# PM12_P3V3.net
KiCad netlist of a schematic drawn in Altium Designer
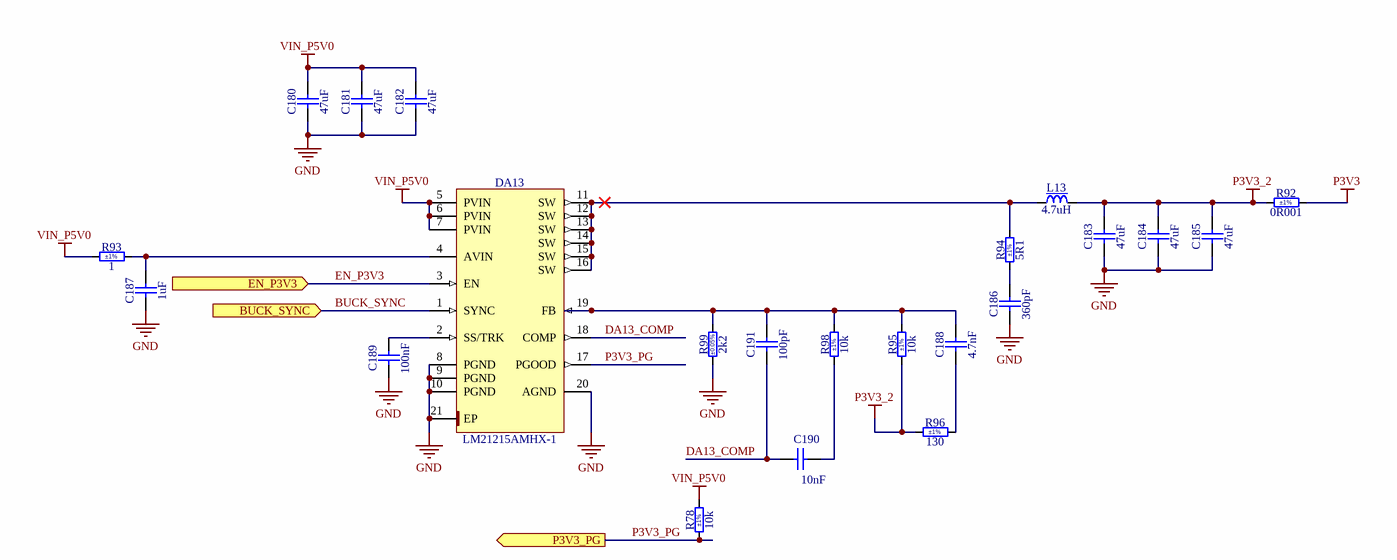
[diagram p0: PM12_P3V3.SchDoc]

(export (version "E")
  (design (tool "Eeschema 10.0.6"))
  (components
    (comp (ref "C180")
      (value "47uF")
      (footprint "CAPC3225X270N")
      (description "Non-polarised capacitor")
      (fields
        (field (name "PART NUMBER") "CC1210_47UF_16V_20%_X5R")
        (field (name "VOLTAGE") "16V")
        (field (name "AUTHOR") "CERN DEM MR")
      )
      (libsource (lib "Capacitors") (part "Capacitor - non polarized"))
    )
    (comp (ref "C181")
      (value "47uF")
      (footprint "CAPC3225X270N")
      (description "Non-polarised capacitor")
      (fields
        (field (name "PART NUMBER") "CC1210_47UF_16V_20%_X5R")
        (field (name "VOLTAGE") "16V")
        (field (name "AUTHOR") "CERN DEM MR")
      )
      (libsource (lib "Capacitors") (part "Capacitor - non polarized"))
    )
    (comp (ref "C182")
      (value "47uF")
      (footprint "CAPC3225X270N")
      (description "Non-polarised capacitor")
      (fields
        (field (name "PART NUMBER") "CC1210_47UF_16V_20%_X5R")
        (field (name "VOLTAGE") "16V")
        (field (name "AUTHOR") "CERN DEM MR")
      )
      (libsource (lib "Capacitors") (part "Capacitor - non polarized"))
    )
    (comp (ref "C183")
      (value "47uF")
      (footprint "CAPC3225X270N")
      (description "Non-polarised capacitor")
      (fields
        (field (name "PART NUMBER") "CC1210_47UF_16V_20%_X5R")
        (field (name "VOLTAGE") "16V")
        (field (name "AUTHOR") "CERN DEM MR")
      )
      (libsource (lib "Capacitors") (part "Capacitor - non polarized"))
    )
    (comp (ref "C184")
      (value "47uF")
      (footprint "CAPC3225X270N")
      (description "Non-polarised capacitor")
      (fields
        (field (name "PART NUMBER") "CC1210_47UF_16V_20%_X5R")
        (field (name "VOLTAGE") "16V")
        (field (name "AUTHOR") "CERN DEM MR")
      )
      (libsource (lib "Capacitors") (part "Capacitor - non polarized"))
    )
    (comp (ref "C185")
      (value "47uF")
      (footprint "CAPC3225X270N")
      (description "Non-polarised capacitor")
      (fields
        (field (name "PART NUMBER") "CC1210_47UF_16V_20%_X5R")
        (field (name "VOLTAGE") "16V")
        (field (name "AUTHOR") "CERN DEM MR")
      )
      (libsource (lib "Capacitors") (part "Capacitor - non polarized"))
    )
    (comp (ref "C186")
      (value "360pF")
      (footprint "CAPC2013X145N")
      (description "Non-polarised capacitor")
      (fields
        (field (name "PART NUMBER") "CC0805_360PF_50V_5%_C0G")
        (field (name "VOLTAGE") "50V")
        (field (name "AUTHOR") "CERN DEM HF")
      )
      (libsource (lib "Capacitors") (part "Capacitor - non polarized"))
    )
    (comp (ref "C187")
      (value "1uF")
      (footprint "CAPC2012X140N")
      (description "Non-polarised capacitor")
      (fields
        (field (name "PART NUMBER") "CC0805_1UF_25V_10%_X7R")
        (field (name "VOLTAGE") "25V")
        (field (name "AUTHOR") "CERN DEM JLC")
      )
      (libsource (lib "Capacitors") (part "Capacitor - non polarized"))
    )
    (comp (ref "C188")
      (value "4.7nF")
      (footprint "CAPC2012X135N")
      (description "Non-polarised capacitor")
      (fields
        (field (name "PART NUMBER") "CC0805_4.7NF_50V_10%_X7R")
        (field (name "VOLTAGE") "50V")
        (field (name "AUTHOR") "CERN DEM JLC")
      )
      (libsource (lib "Capacitors") (part "Capacitor - non polarized"))
    )
    (comp (ref "C189")
      (value "100nF")
      (footprint "CAPC2012X135N")
      (description "Non-polarised capacitor")
      (fields
        (field (name "PART NUMBER") "CC0805_100NF_50V_10%_X7R")
        (field (name "VOLTAGE") "50V")
        (field (name "AUTHOR") "CERN DEM JLC")
      )
      (libsource (lib "Capacitors") (part "Capacitor - non polarized"))
    )
    (comp (ref "C190")
      (value "10nF")
      (footprint "CAPC1005X55N")
      (description "Non-polarised capacitor")
      (fields
        (field (name "PART NUMBER") "CC0402_10NF_25V_10%_X7R")
        (field (name "VOLTAGE") "25V")
        (field (name "AUTHOR") "CERN DEM JLC")
      )
      (libsource (lib "Capacitors") (part "Capacitor - non polarized"))
    )
    (comp (ref "C191")
      (value "100pF")
      (footprint "CAPC2012X135N")
      (description "Non-polarised capacitor")
      (fields
        (field (name "PART NUMBER") "CC0805_100PF_50V_5%_NP0")
        (field (name "VOLTAGE") "50V")
        (field (name "AUTHOR") "CERN DEM JLC")
      )
      (libsource (lib "Capacitors") (part "Capacitor - non polarized"))
    )
    (comp (ref "DA13")
      (value "LM21215AMHX-1")
      (footprint "TEXAS_PWP0020AA")
      (description "2.95-V To 5.5-V, 12-A, Voltage-Mode Synchronous Buck Regulator with Frequency Synchronization")
      (fields (field (name "MANUFACTURER") "TEXAS INSTRUMENTS") (field (name "AUTHOR") "CERN DEM HF"))
      (libsource (lib "ICs And Semiconductors") (part "LM21215"))
    )
    (comp (ref "L13")
      (value "4.7uH")
      (footprint "INDM172170X700N")
      (description "Inductor With Core")
      (fields
        (field (name "PART NUMBER") "IND6767_4.7UH_20%_VISHAY_IHLP-6767GZ-11")
        (field (name "POWER") "30A")
        (field (name "AUTHOR") "CERN DEM HF")
      )
      (libsource (lib "Inductors & Transformers") (part "Inductor With Magnetic core"))
    )
    (comp (ref "R78")
      (value "10k")
      (footprint "RESC1608X55N")
      (description "Resistor - 1%")
      (fields
        (field (name "TOLERANCE") "±1%")
        (field (name "PART NUMBER") "R0603_10K_1%_0.1W_100PPM")
        (field (name "POWER") "0.1W")
        (field (name "AUTHOR") "CERN DEM JLC")
      )
      (libsource (lib "Resistors") (part "Resistor - 1%"))
    )
    (comp (ref "R92")
      (value "0R001")
      (footprint "RESC_BOURNS_CRE2512_0R001-0R004")
      (description "Resistor - 1%")
      (fields
        (field (name "TOLERANCE") "±1%")
        (field (name "PART NUMBER") "R2512_0R001_1%_3W_50PPM_BOURNS_CRE2512")
        (field (name "POWER") "3W")
        (field (name "AUTHOR") "CERN DEM BC")
      )
      (libsource (lib "Resistors") (part "Resistor - 1%"))
    )
    (comp (ref "R93")
      (value "1")
      (footprint "RESC2012X60N")
      (description "Resistor - 1%")
      (fields
        (field (name "TOLERANCE") "±1%")
        (field (name "PART NUMBER") "R0805_1R_1%_0.125W_100PPM")
        (field (name "POWER") "0.125W")
        (field (name "AUTHOR") "CERN DEM HF")
      )
      (libsource (lib "Resistors") (part "Resistor - 1%"))
    )
    (comp (ref "R94")
      (value "5R1")
      (footprint "RESC2012X60N")
      (description "Resistor - 1%")
      (fields
        (field (name "TOLERANCE") "±1%")
        (field (name "PART NUMBER") "R0805_5R1_1%_0.125W_100PPM")
        (field (name "POWER") "0.125W")
        (field (name "AUTHOR") "CERN DEM HF")
      )
      (libsource (lib "Resistors") (part "Resistor - 1%"))
    )
    (comp (ref "R95")
      (value "10k")
      (footprint "RESC1608X55N")
      (description "Resistor - 1%")
      (fields
        (field (name "TOLERANCE") "±1%")
        (field (name "PART NUMBER") "R0603_10K_1%_0.1W_100PPM")
        (field (name "POWER") "0.1W")
        (field (name "AUTHOR") "CERN DEM JLC")
      )
      (libsource (lib "Resistors") (part "Resistor - 1%"))
    )
    (comp (ref "R96")
      (value "130")
      (footprint "RESC2012X60N")
      (description "Resistor - 1%")
      (fields
        (field (name "TOLERANCE") "±1%")
        (field (name "PART NUMBER") "R0805_130R_1%_0.125W_100PPM")
        (field (name "POWER") "0.125W")
        (field (name "AUTHOR") "CERN DEM JLC")
      )
      (libsource (lib "Resistors") (part "Resistor - 1%"))
    )
    (comp (ref "R98")
      (value "10k")
      (footprint "RESC1608X55N")
      (description "Resistor - 1%")
      (fields
        (field (name "TOLERANCE") "±1%")
        (field (name "PART NUMBER") "R0603_10K_1%_0.1W_100PPM")
        (field (name "POWER") "0.1W")
        (field (name "AUTHOR") "CERN DEM JLC")
      )
      (libsource (lib "Resistors") (part "Resistor - 1%"))
    )
    (comp (ref "R99")
      (value "2k2")
      (footprint "RESC2012X60N")
      (description "Resistor - 0.05%")
      (fields
        (field (name "TOLERANCE") "±0.05%")
        (field (name "PART NUMBER") "R0805_2K2_0.05%_0.125W_100PPM")
        (field (name "POWER") "0.125W")
        (field (name "AUTHOR") "CERN DEM JLC")
      )
      (libsource (lib "Resistors") (part "Resistor - 1%"))
    )
  )
  (nets
    (net (code "1") (name "/BUCK_SYNC") (class "Default")
      (node (ref "DA13") (pin "1") (pinfunction "SYNC_1") (pintype "input"))
    )
    (net (code "2") (name "/DA13_COMP") (class "Default")
      (node (ref "C190") (pin "2") (pinfunction "2_2") (pintype "passive"))
      (node (ref "C191") (pin "1") (pinfunction "1_1") (pintype "passive"))
      (node (ref "DA13") (pin "18") (pinfunction "COMP_18") (pintype "output"))
    )
    (net (code "3") (name "/EN_P3V3") (class "Default")
      (node (ref "DA13") (pin "3") (pinfunction "EN_3") (pintype "input"))
    )
    (net (code "4") (name "/P3V3_PG") (class "Default")
      (node (ref "DA13") (pin "17") (pinfunction "PGOOD_17") (pintype "output"))
      (node (ref "R78") (pin "1") (pinfunction "1_1") (pintype "passive"))
    )
    (net (code "5") (name "GND") (class "Default")
      (node (ref "C180") (pin "1") (pinfunction "1_1") (pintype "passive"))
      (node (ref "C181") (pin "1") (pinfunction "1_1") (pintype "passive"))
      (node (ref "C182") (pin "1") (pinfunction "1_1") (pintype "passive"))
      (node (ref "C183") (pin "1") (pinfunction "1_1") (pintype "passive"))
      (node (ref "C184") (pin "1") (pinfunction "1_1") (pintype "passive"))
      (node (ref "C185") (pin "1") (pinfunction "1_1") (pintype "passive"))
      (node (ref "C186") (pin "1") (pinfunction "1_1") (pintype "passive"))
      (node (ref "C187") (pin "1") (pinfunction "1_1") (pintype "passive"))
      (node (ref "C189") (pin "1") (pinfunction "1_1") (pintype "passive"))
      (node (ref "DA13") (pin "10") (pinfunction "PGND_10") (pintype "power_in"))
      (node (ref "DA13") (pin "20") (pinfunction "AGND_20") (pintype "power_in"))
      (node (ref "DA13") (pin "21") (pinfunction "EP_21") (pintype "power_in"))
      (node (ref "DA13") (pin "8") (pinfunction "PGND_8") (pintype "power_in"))
      (node (ref "DA13") (pin "9") (pinfunction "PGND_9") (pintype "power_in"))
      (node (ref "R99") (pin "1") (pinfunction "1_1") (pintype "passive"))
    )
    (net (code "6") (name "Net-(C186-Pad2)") (class "Default")
      (node (ref "C186") (pin "2") (pinfunction "2_2") (pintype "passive"))
      (node (ref "R94") (pin "1") (pinfunction "1_1") (pintype "passive"))
    )
    (net (code "7") (name "Net-(C188-Pad1)") (class "Default")
      (node (ref "C188") (pin "1") (pinfunction "1_1") (pintype "passive"))
      (node (ref "R96") (pin "2") (pinfunction "2_2") (pintype "passive"))
    )
    (net (code "8") (name "Net-(C190-Pad1)") (class "Default")
      (node (ref "C190") (pin "1") (pinfunction "1_1") (pintype "passive"))
      (node (ref "R98") (pin "1") (pinfunction "1_1") (pintype "passive"))
    )
    (net (code "9") (name "Net-(DA13-AVIN)") (class "Default")
      (node (ref "C187") (pin "2") (pinfunction "2_2") (pintype "passive"))
      (node (ref "DA13") (pin "4") (pinfunction "AVIN_4") (pintype "power_in"))
      (node (ref "R93") (pin "2") (pinfunction "2_2") (pintype "passive"))
    )
    (net (code "10") (name "Net-(DA13-FB)") (class "Default")
      (node (ref "C188") (pin "2") (pinfunction "2_2") (pintype "passive"))
      (node (ref "C191") (pin "2") (pinfunction "2_2") (pintype "passive"))
      (node (ref "DA13") (pin "19") (pinfunction "FB_19") (pintype "input"))
      (node (ref "R95") (pin "2") (pinfunction "2_2") (pintype "passive"))
      (node (ref "R98") (pin "2") (pinfunction "2_2") (pintype "passive"))
      (node (ref "R99") (pin "2") (pinfunction "2_2") (pintype "passive"))
    )
    (net (code "11") (name "Net-(DA13-SS{slash}TRK)") (class "Default")
      (node (ref "C189") (pin "2") (pinfunction "2_2") (pintype "passive"))
      (node (ref "DA13") (pin "2") (pinfunction "SS/TRK_2") (pintype "input"))
    )
    (net (code "12") (name "Net-(DA13-SW-Pad11)") (class "Default")
      (node (ref "DA13") (pin "11") (pinfunction "SW_11") (pintype "output"))
      (node (ref "DA13") (pin "12") (pinfunction "SW_12") (pintype "output"))
      (node (ref "DA13") (pin "13") (pinfunction "SW_13") (pintype "output"))
      (node (ref "DA13") (pin "14") (pinfunction "SW_14") (pintype "output"))
      (node (ref "DA13") (pin "15") (pinfunction "SW_15") (pintype "output"))
      (node (ref "DA13") (pin "16") (pinfunction "SW_16") (pintype "output"))
      (node (ref "L13") (pin "1") (pinfunction "1_1") (pintype "passive"))
      (node (ref "R94") (pin "2") (pinfunction "2_2") (pintype "passive"))
    )
    (net (code "13") (name "P3V3") (class "Default")
      (node (ref "R92") (pin "2") (pinfunction "2_2") (pintype "passive"))
    )
    (net (code "14") (name "P3V3_2") (class "Default")
      (node (ref "C183") (pin "2") (pinfunction "2_2") (pintype "passive"))
      (node (ref "C184") (pin "2") (pinfunction "2_2") (pintype "passive"))
      (node (ref "C185") (pin "2") (pinfunction "2_2") (pintype "passive"))
      (node (ref "L13") (pin "2") (pinfunction "2_2") (pintype "passive"))
      (node (ref "R92") (pin "1") (pinfunction "1_1") (pintype "passive"))
      (node (ref "R95") (pin "1") (pinfunction "1_1") (pintype "passive"))
      (node (ref "R96") (pin "1") (pinfunction "1_1") (pintype "passive"))
    )
    (net (code "15") (name "VIN_P5V0") (class "Default")
      (node (ref "C180") (pin "2") (pinfunction "2_2") (pintype "passive"))
      (node (ref "C181") (pin "2") (pinfunction "2_2") (pintype "passive"))
      (node (ref "C182") (pin "2") (pinfunction "2_2") (pintype "passive"))
      (node (ref "DA13") (pin "5") (pinfunction "PVIN_5") (pintype "power_in"))
      (node (ref "DA13") (pin "6") (pinfunction "PVIN_6") (pintype "power_in"))
      (node (ref "DA13") (pin "7") (pinfunction "PVIN_7") (pintype "power_in"))
      (node (ref "R78") (pin "2") (pinfunction "2_2") (pintype "passive"))
      (node (ref "R93") (pin "1") (pinfunction "1_1") (pintype "passive"))
    )
  )
)
